# JTAG.net
KiCad netlist of a schematic drawn in Altium Designer
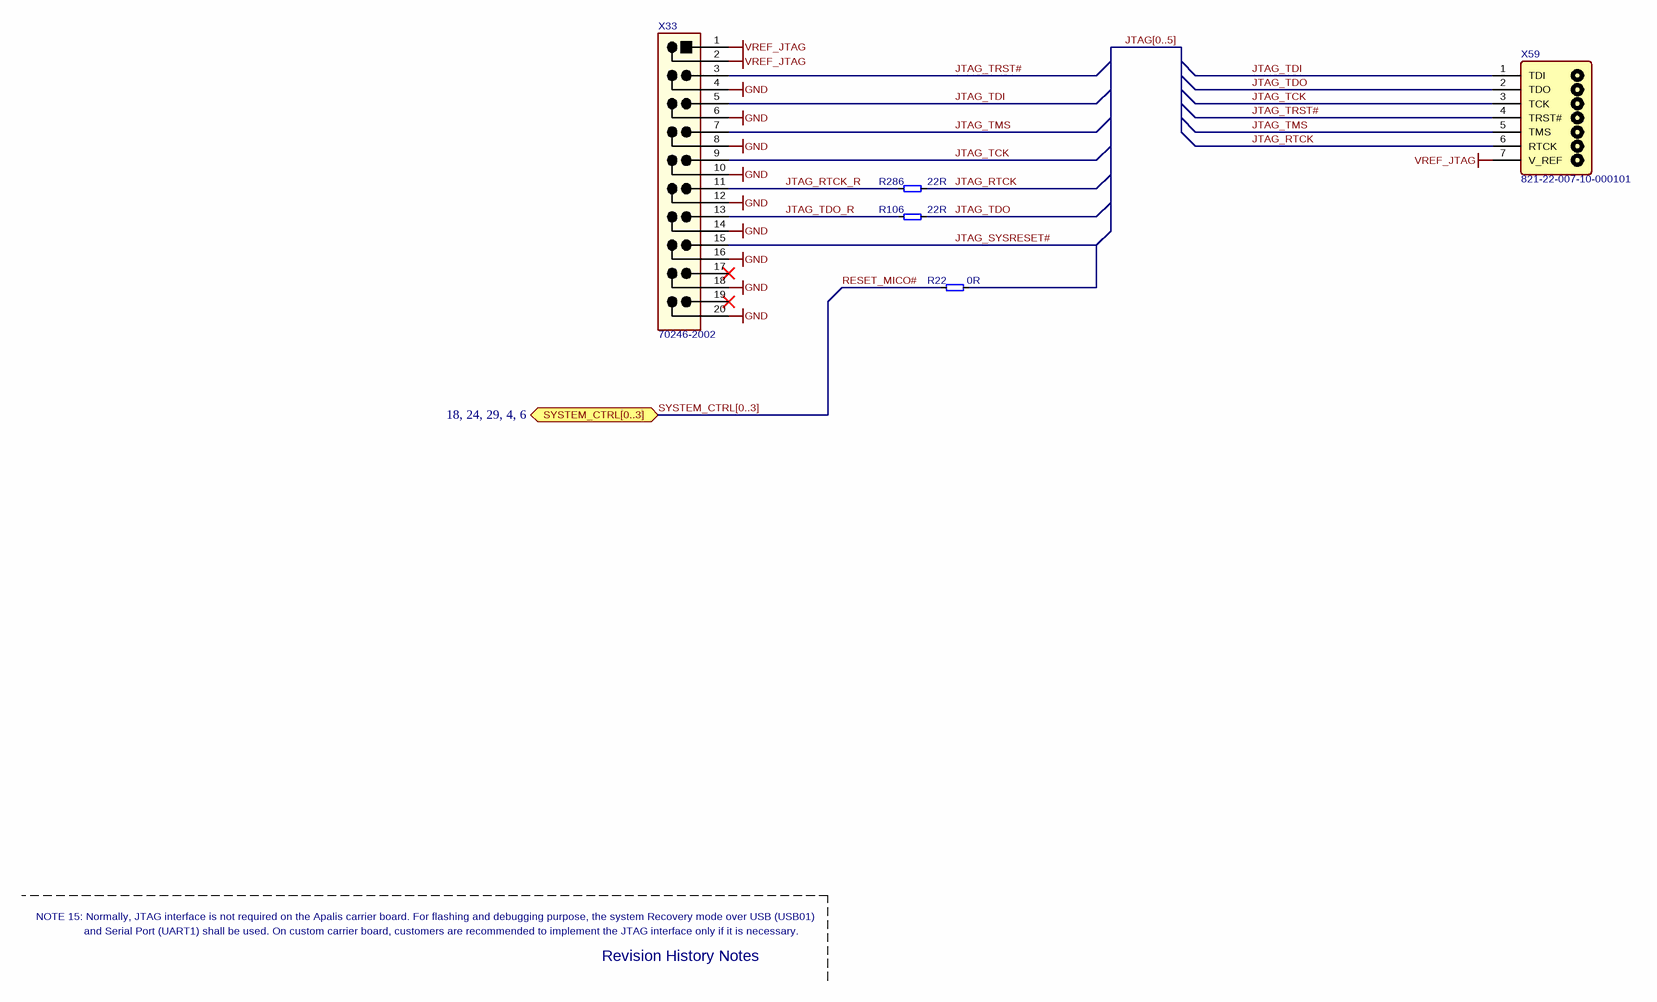
[diagram p0: JTAG.SchDoc]

(export (version "E")
  (design (tool "Eeschema 10.0.6"))
  (components
    (comp (ref "R22")
      (value "0R")
      (footprint "T_RESC0603X30N")
      (description "Resistor 0 ohm 63mW 1% 0603")
      (fields (field (name "TOLERANCE") "1%"))
      (libsource (lib "Apalis Evaluation Board") (part "R-0R-63mW-1%-0603"))
    )
    (comp (ref "R106")
      (value "22R")
      (footprint "T_RESC0603X30N")
      (description "Resistor 22 ohm 63mW 5% 0603")
      (fields (field (name "TOLERANCE") "5%"))
      (libsource (lib "Apalis Evaluation Board") (part "R-22R-63mW-5%-0603"))
    )
    (comp (ref "R286")
      (value "22R")
      (footprint "T_RESC0603X30N")
      (description "Resistor 22 ohm 63mW 5% 0603")
      (fields (field (name "TOLERANCE") "5%"))
      (libsource (lib "Apalis Evaluation Board") (part "R-22R-63mW-5%-0603"))
    )
    (comp (ref "X33")
      (value "70246-2002")
      (footprint "T_Molex_70246-2002")
      (description "Header shrouded male, 2x10 pin 2.54mm pitch")
      (fields (field (name "MANUFACTURER PART NO.") "70246-2002"))
      (libsource (lib "Apalis Evaluation Board") (part "CON-Molex-70246-2002"))
    )
    (comp (ref "X59")
      (value "821-22-007-10-000101")
      (footprint "T_MILL-MAX_821-22-007-10-000101")
      (description "JTAG Pogo pins")
      (fields (field (name "MANUFACTURER PART NO.") "821-22-007-10-000101"))
      (libsource (lib "Apalis Evaluation Board") (part "CON-MM-821-22-007-10-000101"))
    )
  )
  (nets
    (net (code "12") (name "/JTAG_RTCK") (class "Default")
      (node (ref "R286") (pin "2") (pinfunction "2_2") (pintype "passive"))
      (node (ref "X59") (pin "6") (pinfunction "RTCK_6") (pintype "passive"))
    )
    (net (code "13") (name "/JTAG_RTCK_R") (class "Default")
      (node (ref "R286") (pin "1") (pinfunction "1_1") (pintype "passive"))
      (node (ref "X33") (pin "11") (pinfunction "11_11") (pintype "passive"))
    )
    (net (code "14") (name "/JTAG_SYSRESET#") (class "Default")
      (node (ref "R22") (pin "2") (pinfunction "2_2") (pintype "passive"))
      (node (ref "X33") (pin "15") (pinfunction "15_15") (pintype "passive"))
    )
    (net (code "15") (name "/JTAG_TCK") (class "Default")
      (node (ref "X33") (pin "9") (pinfunction "9_9") (pintype "passive"))
      (node (ref "X59") (pin "3") (pinfunction "TCK_3") (pintype "passive"))
    )
    (net (code "16") (name "/JTAG_TDI") (class "Default")
      (node (ref "X33") (pin "5") (pinfunction "5_5") (pintype "passive"))
      (node (ref "X59") (pin "1") (pinfunction "TDI_1") (pintype "passive"))
    )
    (net (code "17") (name "/JTAG_TDO") (class "Default")
      (node (ref "R106") (pin "2") (pinfunction "2_2") (pintype "passive"))
      (node (ref "X59") (pin "2") (pinfunction "TDO_2") (pintype "passive"))
    )
    (net (code "18") (name "/JTAG_TDO_R") (class "Default")
      (node (ref "R106") (pin "1") (pinfunction "1_1") (pintype "passive"))
      (node (ref "X33") (pin "13") (pinfunction "13_13") (pintype "passive"))
    )
    (net (code "19") (name "/JTAG_TMS") (class "Default")
      (node (ref "X33") (pin "7") (pinfunction "7_7") (pintype "passive"))
      (node (ref "X59") (pin "5") (pinfunction "TMS_5") (pintype "passive"))
    )
    (net (code "20") (name "/JTAG_TRST#") (class "Default")
      (node (ref "X33") (pin "3") (pinfunction "3_3") (pintype "passive"))
      (node (ref "X59") (pin "4") (pinfunction "TRST#_4") (pintype "passive"))
    )
    (net (code "21") (name "/RESET_MICO#") (class "Default")
      (node (ref "R22") (pin "1") (pinfunction "1_1") (pintype "passive"))
    )
    (net (code "23") (name "GND") (class "Default")
      (node (ref "X33") (pin "10") (pinfunction "10_10") (pintype "passive"))
      (node (ref "X33") (pin "12") (pinfunction "12_12") (pintype "passive"))
      (node (ref "X33") (pin "14") (pinfunction "14_14") (pintype "passive"))
      (node (ref "X33") (pin "16") (pinfunction "16_16") (pintype "passive"))
      (node (ref "X33") (pin "18") (pinfunction "18_18") (pintype "passive"))
      (node (ref "X33") (pin "20") (pinfunction "20_20") (pintype "passive"))
      (node (ref "X33") (pin "4") (pinfunction "4_4") (pintype "passive"))
      (node (ref "X33") (pin "6") (pinfunction "6_6") (pintype "passive"))
      (node (ref "X33") (pin "8") (pinfunction "8_8") (pintype "passive"))
    )
    (net (code "24") (name "VREF_JTAG") (class "Default")
      (node (ref "X33") (pin "1") (pinfunction "1_1") (pintype "passive"))
      (node (ref "X33") (pin "2") (pinfunction "2_2") (pintype "passive"))
      (node (ref "X59") (pin "7") (pinfunction "V_REF_7") (pintype "passive"))
    )
    (net (code "25") (name "unconnected-(X33-Pad17)") (class "Default")
      (node (ref "X33") (pin "17") (pinfunction "17_17") (pintype "passive+no_connect"))
    )
    (net (code "26") (name "unconnected-(X33-Pad19)") (class "Default")
      (node (ref "X33") (pin "19") (pinfunction "19_19") (pintype "passive+no_connect"))
    )
  )
)
